# LCDK.net
KiCad netlist of a schematic drawn in EAGLE
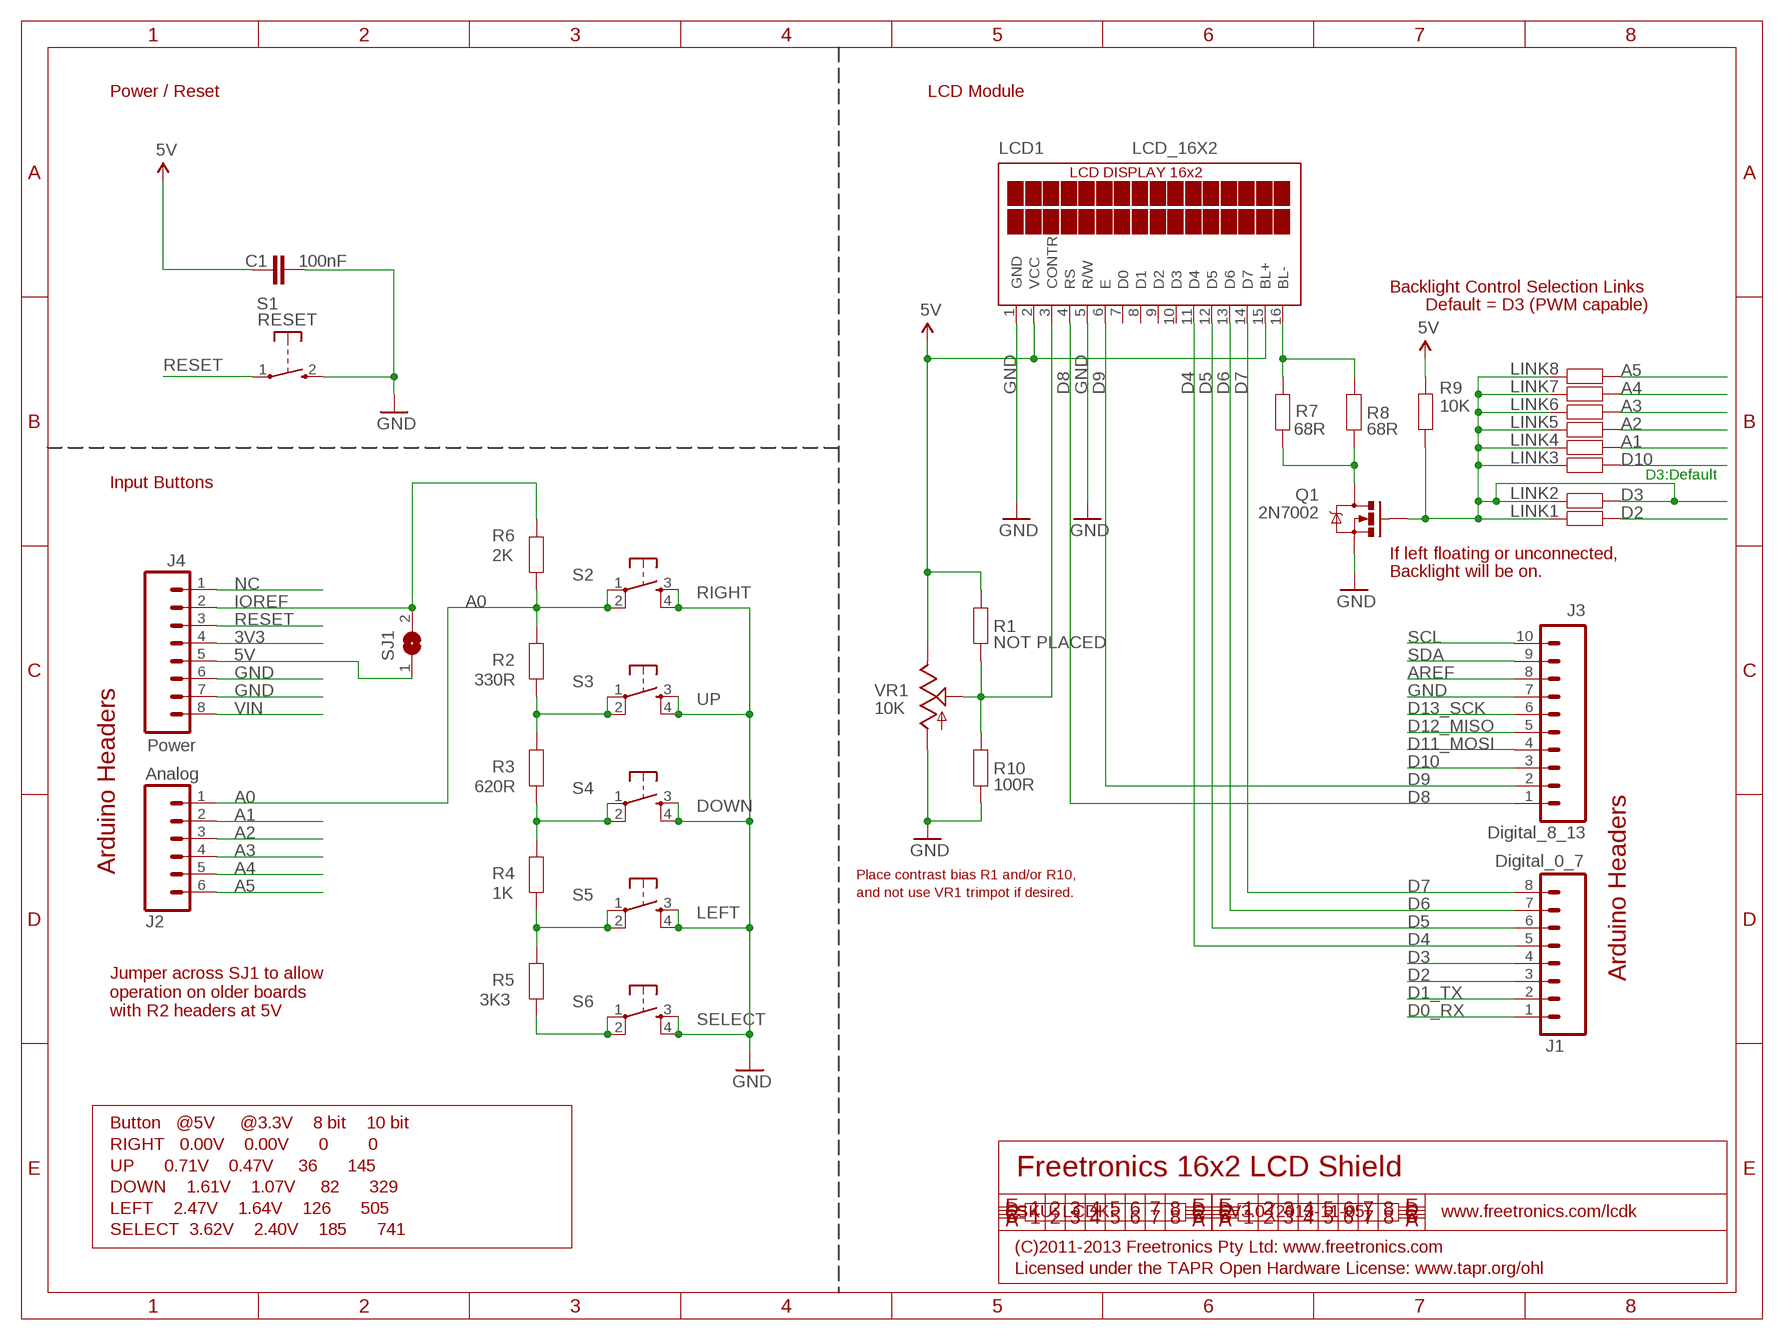
[diagram p0: schematic, sheet 1]

(export (version "E")
  (design (tool "Eeschema 10.0.6"))
  (components
    (comp (ref "C1")
      (value "100nF")
      (footprint "eagle-import:0603")
      (libsource (lib "eagle-import") (part "CAP0603"))
    )
    (comp (ref "J1")
      (value "Digital_0_7")
      (footprint "eagle-import:1X08")
      (libsource (lib "eagle-import") (part "M08"))
    )
    (comp (ref "J2")
      (value "Analog")
      (footprint "eagle-import:1X06")
      (libsource (lib "eagle-import") (part "M06SIP"))
    )
    (comp (ref "J3")
      (value "Digital_8_13")
      (footprint "eagle-import:1X10")
      (libsource (lib "eagle-import") (part "M100.1"))
    )
    (comp (ref "J4")
      (value "Power")
      (footprint "eagle-import:1X08")
      (libsource (lib "eagle-import") (part "M08"))
    )
    (comp (ref "LCD1")
      (value "LCD_16X2")
      (footprint "eagle-import:LCD_16X2_REAR")
      (libsource (lib "eagle-import") (part "LCD_16X2_NEWLCD_16X2"))
    )
    (comp (ref "LINK1")
      (value "RESISTOR0603")
      (footprint "eagle-import:0603")
      (libsource (lib "eagle-import") (part "RESISTOR0603"))
    )
    (comp (ref "LINK2")
      (value "RESISTOR0603")
      (footprint "eagle-import:0603")
      (libsource (lib "eagle-import") (part "RESISTOR0603"))
    )
    (comp (ref "LINK3")
      (value "RESISTOR0603")
      (footprint "eagle-import:0603")
      (libsource (lib "eagle-import") (part "RESISTOR0603"))
    )
    (comp (ref "LINK4")
      (value "RESISTOR0603")
      (footprint "eagle-import:0603")
      (libsource (lib "eagle-import") (part "RESISTOR0603"))
    )
    (comp (ref "LINK5")
      (value "RESISTOR0603")
      (footprint "eagle-import:0603")
      (libsource (lib "eagle-import") (part "RESISTOR0603"))
    )
    (comp (ref "LINK6")
      (value "RESISTOR0603")
      (footprint "eagle-import:0603")
      (libsource (lib "eagle-import") (part "RESISTOR0603"))
    )
    (comp (ref "LINK7")
      (value "RESISTOR0603")
      (footprint "eagle-import:0603")
      (libsource (lib "eagle-import") (part "RESISTOR0603"))
    )
    (comp (ref "LINK8")
      (value "RESISTOR0603")
      (footprint "eagle-import:0603")
      (libsource (lib "eagle-import") (part "RESISTOR0603"))
    )
    (comp (ref "Q1")
      (value "2N7002")
      (footprint "eagle-import:SOT23-3")
      (libsource (lib "eagle-import") (part "MOSFET-NCHANNELSMD"))
    )
    (comp (ref "R1")
      (value "NOT PLACED")
      (footprint "eagle-import:0603")
      (libsource (lib "eagle-import") (part "RESISTOR0603"))
    )
    (comp (ref "R2")
      (value "330R")
      (footprint "eagle-import:0603")
      (libsource (lib "eagle-import") (part "RESISTOR0603"))
    )
    (comp (ref "R3")
      (value "620R")
      (footprint "eagle-import:0603")
      (libsource (lib "eagle-import") (part "RESISTOR0603"))
    )
    (comp (ref "R4")
      (value "1K")
      (footprint "eagle-import:0603")
      (libsource (lib "eagle-import") (part "RESISTOR0603"))
    )
    (comp (ref "R5")
      (value "3K3")
      (footprint "eagle-import:0603")
      (libsource (lib "eagle-import") (part "RESISTOR0603"))
    )
    (comp (ref "R6")
      (value "2K")
      (footprint "eagle-import:0603")
      (libsource (lib "eagle-import") (part "RESISTOR0603"))
    )
    (comp (ref "R7")
      (value "68R")
      (footprint "eagle-import:0603")
      (libsource (lib "eagle-import") (part "RESISTOR0603"))
    )
    (comp (ref "R8")
      (value "68R")
      (footprint "eagle-import:0603")
      (libsource (lib "eagle-import") (part "RESISTOR0603"))
    )
    (comp (ref "R9")
      (value "10K")
      (footprint "eagle-import:0603")
      (libsource (lib "eagle-import") (part "RESISTOR0603"))
    )
    (comp (ref "R10")
      (value "100R")
      (footprint "eagle-import:0603")
      (libsource (lib "eagle-import") (part "RESISTOR0603"))
    )
    (comp (ref "S1")
      (value "RESET")
      (footprint "eagle-import:TACTILE_SWITCH_SMD_2PIN_TINY")
      (libsource (lib "eagle-import") (part "TAC_SWITCH_2PIN"))
    )
    (comp (ref "S2")
      (value "RIGHT")
      (footprint "eagle-import:TACTILE-PTH-4.5MM")
      (libsource (lib "eagle-import") (part "TAC_SWITCH"))
    )
    (comp (ref "S3")
      (value "UP")
      (footprint "eagle-import:TACTILE-PTH-4.5MM")
      (libsource (lib "eagle-import") (part "TAC_SWITCH"))
    )
    (comp (ref "S4")
      (value "DOWN")
      (footprint "eagle-import:TACTILE-PTH-4.5MM")
      (libsource (lib "eagle-import") (part "TAC_SWITCH"))
    )
    (comp (ref "S5")
      (value "LEFT")
      (footprint "eagle-import:TACTILE-PTH-4.5MM")
      (libsource (lib "eagle-import") (part "TAC_SWITCH"))
    )
    (comp (ref "S6")
      (value "SELECT")
      (footprint "eagle-import:TACTILE-PTH-4.5MM")
      (libsource (lib "eagle-import") (part "TAC_SWITCH"))
    )
    (comp (ref "SJ1")
      (value "SJN")
      (footprint "eagle-import:SJ")
      (libsource (lib "eagle-import") (part "SJN"))
    )
    (comp (ref "VR1")
      (value "10K")
      (footprint "eagle-import:RTRIM3314J")
      (libsource (lib "eagle-import") (part "POTTRIMPOT_SMT_BOURNS_3314J"))
    )
  )
  (nets
    (net (code "1") (name "/3V3") (class "Default")
      (node (ref "J4") (pin "4") (pinfunction "4_4") (pintype "passive"))
    )
    (net (code "2") (name "/A0") (class "Default")
      (node (ref "J2") (pin "1") (pinfunction "1_1") (pintype "passive"))
      (node (ref "R2") (pin "2") (pinfunction "2_2") (pintype "passive"))
      (node (ref "R6") (pin "1") (pinfunction "1_1") (pintype "passive"))
      (node (ref "S2") (pin "1") (pinfunction "1_1") (pintype "passive"))
      (node (ref "S2") (pin "2") (pinfunction "2_2") (pintype "passive"))
    )
    (net (code "3") (name "/A1") (class "Default")
      (node (ref "J2") (pin "2") (pinfunction "2_2") (pintype "passive"))
      (node (ref "LINK4") (pin "1") (pinfunction "1_1") (pintype "passive"))
    )
    (net (code "4") (name "/A2") (class "Default")
      (node (ref "J2") (pin "3") (pinfunction "3_3") (pintype "passive"))
      (node (ref "LINK5") (pin "1") (pinfunction "1_1") (pintype "passive"))
    )
    (net (code "5") (name "/A3") (class "Default")
      (node (ref "J2") (pin "4") (pinfunction "4_4") (pintype "passive"))
      (node (ref "LINK6") (pin "1") (pinfunction "1_1") (pintype "passive"))
    )
    (net (code "6") (name "/A4") (class "Default")
      (node (ref "J2") (pin "5") (pinfunction "5_5") (pintype "passive"))
      (node (ref "LINK7") (pin "1") (pinfunction "1_1") (pintype "passive"))
    )
    (net (code "7") (name "/A5") (class "Default")
      (node (ref "J2") (pin "6") (pinfunction "6_6") (pintype "passive"))
      (node (ref "LINK8") (pin "1") (pinfunction "1_1") (pintype "passive"))
    )
    (net (code "8") (name "/AREF") (class "Default")
      (node (ref "J3") (pin "8") (pinfunction "8_8") (pintype "passive"))
    )
    (net (code "9") (name "/D0_RX") (class "Default")
      (node (ref "J1") (pin "1") (pinfunction "1_1") (pintype "passive"))
    )
    (net (code "10") (name "/D1_TX") (class "Default")
      (node (ref "J1") (pin "2") (pinfunction "2_2") (pintype "passive"))
    )
    (net (code "11") (name "/D2") (class "Default")
      (node (ref "J1") (pin "3") (pinfunction "3_3") (pintype "passive"))
      (node (ref "LINK1") (pin "1") (pinfunction "1_1") (pintype "passive"))
    )
    (net (code "12") (name "/D3") (class "Default")
      (node (ref "J1") (pin "4") (pinfunction "4_4") (pintype "passive"))
      (node (ref "LINK1") (pin "2") (pinfunction "2_2") (pintype "passive"))
      (node (ref "LINK2") (pin "1") (pinfunction "1_1") (pintype "passive"))
      (node (ref "LINK2") (pin "2") (pinfunction "2_2") (pintype "passive"))
      (node (ref "LINK3") (pin "2") (pinfunction "2_2") (pintype "passive"))
      (node (ref "LINK4") (pin "2") (pinfunction "2_2") (pintype "passive"))
      (node (ref "LINK5") (pin "2") (pinfunction "2_2") (pintype "passive"))
      (node (ref "LINK6") (pin "2") (pinfunction "2_2") (pintype "passive"))
      (node (ref "LINK7") (pin "2") (pinfunction "2_2") (pintype "passive"))
      (node (ref "LINK8") (pin "2") (pinfunction "2_2") (pintype "passive"))
      (node (ref "Q1") (pin "1") (pinfunction "G_1") (pintype "passive"))
      (node (ref "R9") (pin "2") (pinfunction "2_2") (pintype "passive"))
    )
    (net (code "13") (name "/D4") (class "Default")
      (node (ref "J1") (pin "5") (pinfunction "5_5") (pintype "passive"))
      (node (ref "LCD1") (pin "11") (pinfunction "D4_11") (pintype "input"))
    )
    (net (code "14") (name "/D5") (class "Default")
      (node (ref "J1") (pin "6") (pinfunction "6_6") (pintype "passive"))
      (node (ref "LCD1") (pin "12") (pinfunction "D5_12") (pintype "input"))
    )
    (net (code "15") (name "/D6") (class "Default")
      (node (ref "J1") (pin "7") (pinfunction "7_7") (pintype "passive"))
      (node (ref "LCD1") (pin "13") (pinfunction "D6_13") (pintype "input"))
    )
    (net (code "16") (name "/D7") (class "Default")
      (node (ref "J1") (pin "8") (pinfunction "8_8") (pintype "passive"))
      (node (ref "LCD1") (pin "14") (pinfunction "D7_14") (pintype "input"))
    )
    (net (code "17") (name "/D8") (class "Default")
      (node (ref "J3") (pin "1") (pinfunction "1_1") (pintype "passive"))
      (node (ref "LCD1") (pin "4") (pinfunction "RS_4") (pintype "input"))
    )
    (net (code "18") (name "/D9") (class "Default")
      (node (ref "J3") (pin "2") (pinfunction "2_2") (pintype "passive"))
      (node (ref "LCD1") (pin "6") (pinfunction "E_6") (pintype "input"))
    )
    (net (code "19") (name "/D10") (class "Default")
      (node (ref "J3") (pin "3") (pinfunction "3_3") (pintype "passive"))
      (node (ref "LINK3") (pin "1") (pinfunction "1_1") (pintype "passive"))
    )
    (net (code "20") (name "/D11_MOSI") (class "Default")
      (node (ref "J3") (pin "4") (pinfunction "4_4") (pintype "passive"))
    )
    (net (code "21") (name "/D12_MISO") (class "Default")
      (node (ref "J3") (pin "5") (pinfunction "5_5") (pintype "passive"))
    )
    (net (code "22") (name "/D13_SCK") (class "Default")
      (node (ref "J3") (pin "6") (pinfunction "6_6") (pintype "passive"))
    )
    (net (code "23") (name "/IOREF") (class "Default")
      (node (ref "J4") (pin "2") (pinfunction "2_2") (pintype "passive"))
      (node (ref "R6") (pin "2") (pinfunction "2_2") (pintype "passive"))
      (node (ref "SJ1") (pin "2") (pinfunction "2_2") (pintype "passive"))
    )
    (net (code "24") (name "/NC") (class "Default")
      (node (ref "J4") (pin "1") (pinfunction "1_1") (pintype "passive"))
    )
    (net (code "25") (name "/RESET") (class "Default")
      (node (ref "J4") (pin "3") (pinfunction "3_3") (pintype "passive"))
      (node (ref "S1") (pin "1") (pinfunction "P_1") (pintype "passive"))
    )
    (net (code "26") (name "/SCL") (class "Default")
      (node (ref "J3") (pin "10") (pinfunction "10_10") (pintype "passive"))
    )
    (net (code "27") (name "/SDA") (class "Default")
      (node (ref "J3") (pin "9") (pinfunction "9_9") (pintype "passive"))
    )
    (net (code "28") (name "/VIN") (class "Default")
      (node (ref "J4") (pin "8") (pinfunction "8_8") (pintype "passive"))
    )
    (net (code "29") (name "5V") (class "Default")
      (node (ref "C1") (pin "1") (pinfunction "1_1") (pintype "passive"))
      (node (ref "J4") (pin "5") (pinfunction "5_5") (pintype "passive"))
      (node (ref "LCD1") (pin "15") (pinfunction "BL+_15") (pintype "input"))
      (node (ref "LCD1") (pin "2") (pinfunction "VCC_2") (pintype "power_in"))
      (node (ref "R1") (pin "2") (pinfunction "2_2") (pintype "passive"))
      (node (ref "R9") (pin "1") (pinfunction "1_1") (pintype "passive"))
      (node (ref "SJ1") (pin "1") (pinfunction "1_1") (pintype "passive"))
      (node (ref "VR1") (pin "2") (pinfunction "E_2") (pintype "passive"))
    )
    (net (code "30") (name "GND") (class "Default")
      (node (ref "C1") (pin "2") (pinfunction "2_2") (pintype "passive"))
      (node (ref "J3") (pin "7") (pinfunction "7_7") (pintype "passive"))
      (node (ref "J4") (pin "6") (pinfunction "6_6") (pintype "passive"))
      (node (ref "J4") (pin "7") (pinfunction "7_7") (pintype "passive"))
      (node (ref "LCD1") (pin "1") (pinfunction "GND_1") (pintype "power_in"))
      (node (ref "LCD1") (pin "5") (pinfunction "R/W_5") (pintype "input"))
      (node (ref "Q1") (pin "2") (pinfunction "S_2") (pintype "passive"))
      (node (ref "R10") (pin "1") (pinfunction "1_1") (pintype "passive"))
      (node (ref "S1") (pin "2") (pinfunction "S_2") (pintype "passive"))
      (node (ref "S2") (pin "3") (pinfunction "3_3") (pintype "passive"))
      (node (ref "S2") (pin "4") (pinfunction "4_4") (pintype "passive"))
      (node (ref "S3") (pin "3") (pinfunction "3_3") (pintype "passive"))
      (node (ref "S3") (pin "4") (pinfunction "4_4") (pintype "passive"))
      (node (ref "S4") (pin "3") (pinfunction "3_3") (pintype "passive"))
      (node (ref "S4") (pin "4") (pinfunction "4_4") (pintype "passive"))
      (node (ref "S5") (pin "3") (pinfunction "3_3") (pintype "passive"))
      (node (ref "S5") (pin "4") (pinfunction "4_4") (pintype "passive"))
      (node (ref "S6") (pin "3") (pinfunction "3_3") (pintype "passive"))
      (node (ref "S6") (pin "4") (pinfunction "4_4") (pintype "passive"))
      (node (ref "VR1") (pin "1") (pinfunction "A_1") (pintype "passive"))
    )
    (net (code "31") (name "Net-(LCD1-BL-)") (class "Default")
      (node (ref "LCD1") (pin "16") (pinfunction "BL-_16") (pintype "input"))
      (node (ref "R7") (pin "2") (pinfunction "2_2") (pintype "passive"))
      (node (ref "R8") (pin "2") (pinfunction "2_2") (pintype "passive"))
    )
    (net (code "32") (name "Net-(LCD1-CONTR)") (class "Default")
      (node (ref "LCD1") (pin "3") (pinfunction "CONTR_3") (pintype "input"))
      (node (ref "R1") (pin "1") (pinfunction "1_1") (pintype "passive"))
      (node (ref "R10") (pin "2") (pinfunction "2_2") (pintype "passive"))
      (node (ref "VR1") (pin "W") (pinfunction "S_W") (pintype "passive"))
    )
    (net (code "33") (name "Net-(Q1-D)") (class "Default")
      (node (ref "Q1") (pin "3") (pinfunction "D_3") (pintype "passive"))
      (node (ref "R7") (pin "1") (pinfunction "1_1") (pintype "passive"))
      (node (ref "R8") (pin "1") (pinfunction "1_1") (pintype "passive"))
    )
    (net (code "34") (name "Net-(R2-Pad1)") (class "Default")
      (node (ref "R2") (pin "1") (pinfunction "1_1") (pintype "passive"))
      (node (ref "R3") (pin "2") (pinfunction "2_2") (pintype "passive"))
      (node (ref "S3") (pin "1") (pinfunction "1_1") (pintype "passive"))
      (node (ref "S3") (pin "2") (pinfunction "2_2") (pintype "passive"))
    )
    (net (code "35") (name "Net-(R3-Pad1)") (class "Default")
      (node (ref "R3") (pin "1") (pinfunction "1_1") (pintype "passive"))
      (node (ref "R4") (pin "2") (pinfunction "2_2") (pintype "passive"))
      (node (ref "S4") (pin "1") (pinfunction "1_1") (pintype "passive"))
      (node (ref "S4") (pin "2") (pinfunction "2_2") (pintype "passive"))
    )
    (net (code "36") (name "Net-(R4-Pad1)") (class "Default")
      (node (ref "R4") (pin "1") (pinfunction "1_1") (pintype "passive"))
      (node (ref "R5") (pin "2") (pinfunction "2_2") (pintype "passive"))
      (node (ref "S5") (pin "1") (pinfunction "1_1") (pintype "passive"))
      (node (ref "S5") (pin "2") (pinfunction "2_2") (pintype "passive"))
    )
    (net (code "37") (name "Net-(R5-Pad1)") (class "Default")
      (node (ref "R5") (pin "1") (pinfunction "1_1") (pintype "passive"))
      (node (ref "S6") (pin "1") (pinfunction "1_1") (pintype "passive"))
      (node (ref "S6") (pin "2") (pinfunction "2_2") (pintype "passive"))
    )
    (net (code "38") (name "unconnected-(LCD1-D0-Pad7)") (class "Default")
      (node (ref "LCD1") (pin "7") (pinfunction "D0_7") (pintype "input"))
    )
    (net (code "39") (name "unconnected-(LCD1-D1-Pad8)") (class "Default")
      (node (ref "LCD1") (pin "8") (pinfunction "D1_8") (pintype "input"))
    )
    (net (code "40") (name "unconnected-(LCD1-D2-Pad9)") (class "Default")
      (node (ref "LCD1") (pin "9") (pinfunction "D2_9") (pintype "input"))
    )
    (net (code "41") (name "unconnected-(LCD1-D3-Pad10)") (class "Default")
      (node (ref "LCD1") (pin "10") (pinfunction "D3_10") (pintype "input"))
    )
  )
)
